# ATMEL328P.net
KiCad netlist of a schematic drawn in Altium Designer
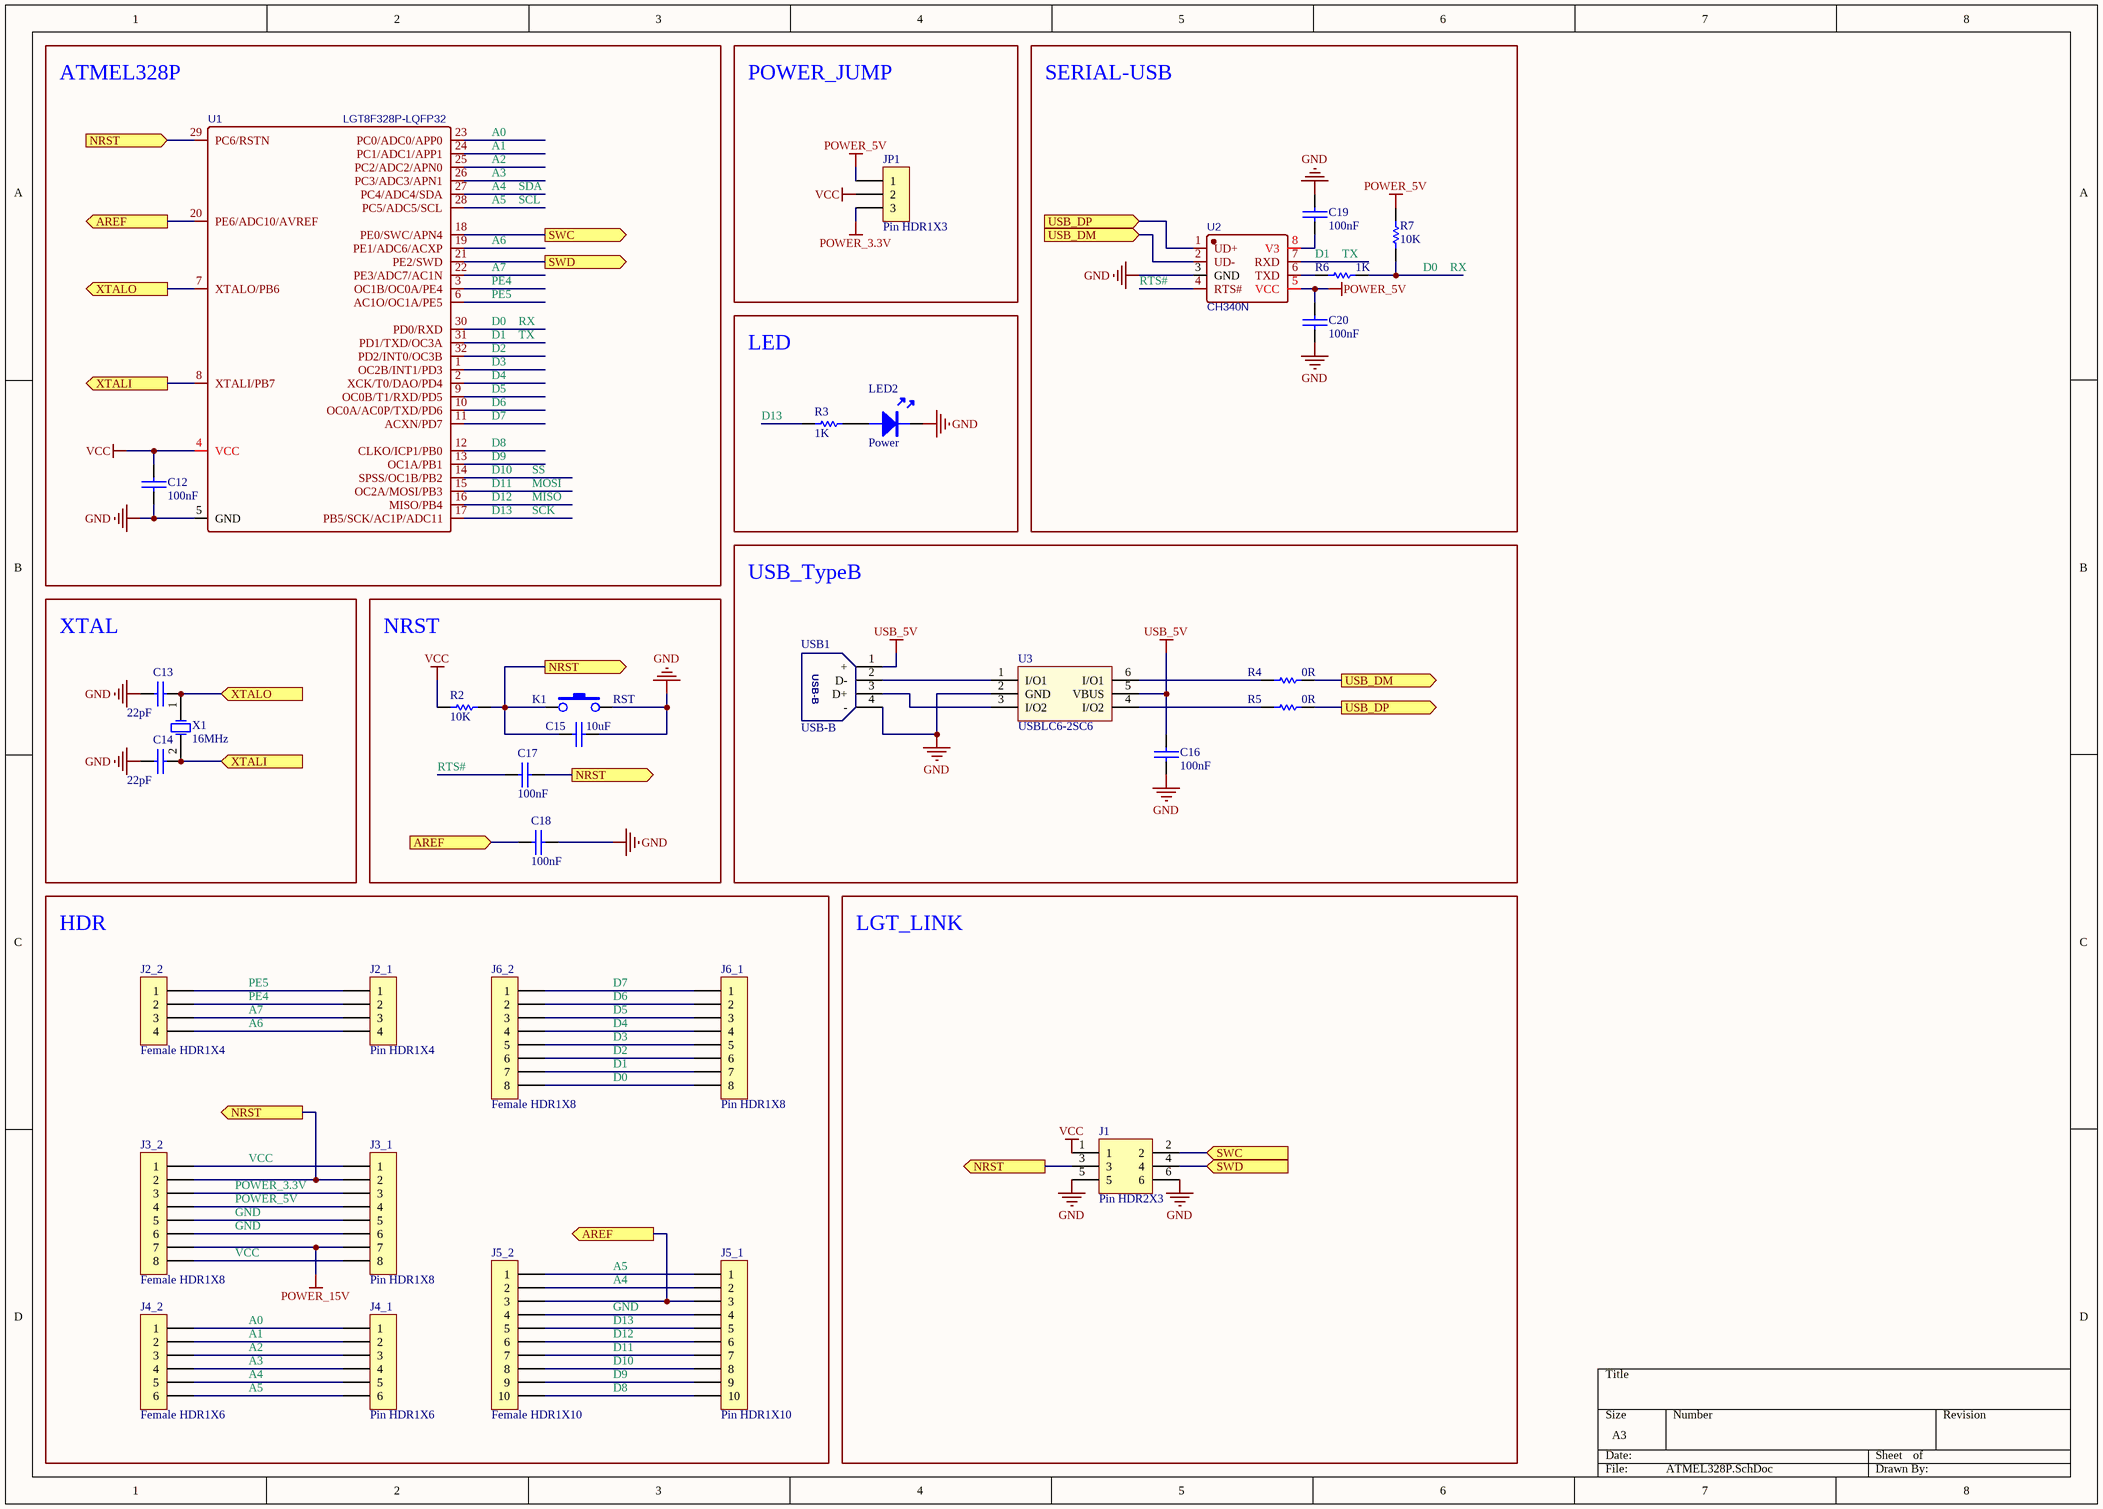
[diagram p0: ATMEL328P.SchDoc]

(export (version "E")
  (design (tool "Eeschema 10.0.6"))
  (components
    (comp (ref "C12")
      (value "100nF")
      (footprint "0603C")
      (description "无极性电容")
      (libsource (lib "电容") (part "CAP"))
    )
    (comp (ref "C13") (value "22pF") (footprint "0603C") (libsource (lib "HSunWriterIII_v3.5") (part "C")))
    (comp (ref "C14") (value "22pF") (footprint "0603C") (libsource (lib "HSunWriterIII_v3.5") (part "C")))
    (comp (ref "C15")
      (value "10uF")
      (footprint "0603C")
      (description "无极性电容")
      (libsource (lib "电容") (part "CAP"))
    )
    (comp (ref "C16")
      (value "100nF")
      (footprint "0603C")
      (description "无极性电容")
      (libsource (lib "电容") (part "CAP"))
    )
    (comp (ref "C17")
      (value "100nF")
      (footprint "0603C")
      (description "无极性电容")
      (libsource (lib "电容") (part "CAP"))
    )
    (comp (ref "C18")
      (value "100nF")
      (footprint "0603C")
      (description "无极性电容")
      (libsource (lib "电容") (part "CAP"))
    )
    (comp (ref "C19")
      (value "100nF")
      (footprint "0603C")
      (description "无极性电容")
      (libsource (lib "电容") (part "CAP"))
    )
    (comp (ref "C20")
      (value "100nF")
      (footprint "0603C")
      (description "无极性电容")
      (libsource (lib "电容") (part "CAP"))
    )
    (comp (ref "J1")
      (value "Pin HDR2X3")
      (footprint "Pin HDR2X3/2.54mm-S")
      (libsource (lib "排针") (part "Pin HDR2X3"))
    )
    (comp (ref "J2_1")
      (value "Pin HDR1X4")
      (footprint "Pin HDR1X4/2.54mm-S")
      (libsource (lib "排针") (part "Pin HDR1X4"))
    )
    (comp (ref "J2_2")
      (value "Female HDR1X4")
      (footprint "Fe-HDR1X4/2.54-S")
      (libsource (lib "排母") (part "Female HDR1X4"))
    )
    (comp (ref "J3_1")
      (value "Pin HDR1X8")
      (footprint "Pin HDR1X8/2.54mm-S")
      (libsource (lib "排针") (part "Pin HDR1X8"))
    )
    (comp (ref "J3_2")
      (value "Female HDR1X8")
      (footprint "Fe-HDR1X8/2.54-S")
      (libsource (lib "排母") (part "Female HDR1X8"))
    )
    (comp (ref "J4_1")
      (value "Pin HDR1X6")
      (footprint "Pin HDR1X6/2.54mm-S")
      (libsource (lib "排针") (part "Pin HDR1X6"))
    )
    (comp (ref "J4_2")
      (value "Female HDR1X6")
      (footprint "Fe-HDR1X6/2.54-S")
      (libsource (lib "排母") (part "Female HDR1X6"))
    )
    (comp (ref "J5_1")
      (value "Pin HDR1X10")
      (footprint "Pin HDR1X10/2.54mm-S")
      (libsource (lib "排针") (part "Pin HDR1X10"))
    )
    (comp (ref "J5_2")
      (value "Female HDR1X10")
      (footprint "Fe-HDR1X10/2.54-S")
      (libsource (lib "排母") (part "Female HDR1X10"))
    )
    (comp (ref "J6_1")
      (value "Pin HDR1X8")
      (footprint "Pin HDR1X8/2.54mm-S")
      (libsource (lib "排针") (part "Pin HDR1X8"))
    )
    (comp (ref "J6_2")
      (value "Female HDR1X8")
      (footprint "Fe-HDR1X8/2.54-S")
      (libsource (lib "排母") (part "Female HDR1X8"))
    )
    (comp (ref "JP1")
      (value "Pin HDR1X3")
      (footprint "Pin HDR1X3/2.54mm-S")
      (libsource (lib "排针") (part "Pin HDR1X3"))
    )
    (comp (ref "K1") (value "RST") (footprint "SMD-3X6X2.5") (libsource (lib "轻触开关") (part "KEY")))
    (comp (ref "LED2") (value "Power") (footprint "LED-0805G") (libsource (lib "LED") (part "LED")))
    (comp (ref "R2") (value "10K") (footprint "0603R") (libsource (lib "电阻") (part "RES")))
    (comp (ref "R3") (value "1K") (footprint "0603R") (libsource (lib "电阻") (part "RES")))
    (comp (ref "R4") (value "0R") (footprint "0603R") (libsource (lib "电阻") (part "RES")))
    (comp (ref "R5") (value "0R") (footprint "0603R") (libsource (lib "电阻") (part "RES")))
    (comp (ref "R6") (value "1K") (footprint "0603R") (libsource (lib "电阻") (part "RES")))
    (comp (ref "R7") (value "10K") (footprint "0603R") (libsource (lib "电阻") (part "RES")))
    (comp (ref "U1")
      (value "LGT8F328P-LQFP32")
      (footprint "LQFP32")
      (fields (field (name "CONTRIBUTOR") "梦之精灵影像设计协会"))
      (libsource (lib "Sheet_2023-03-16") (part "LGT8F328P-LQFP32"))
    )
    (comp (ref "U2")
      (value "CH340N")
      (footprint "SOP8")
      (fields (field (name "BOM_SUPPLIER PART") "C506813") (field (name "CONTRIBUTOR") "梦之精灵影像设计协会"))
      (libsource (lib "Sheet_2023-03-16") (part "CH340N"))
    )
    (comp (ref "U3") (value "USBLC6-2SC6") (footprint "SOT23-6") (libsource (lib "LIB") (part "USBLC6-2SC6")))
    (comp (ref "USB1") (value "USB-B") (footprint "USB-B/S_A") (libsource (lib "USB") (part "USB-B")))
    (comp (ref "X1")
      (value "16MHz")
      (footprint "OSC HC-49S")
      (description "Crystal Oscillator")
      (fields (field (name "PUBLISHER") "Altium Limited"))
      (libsource (lib "HSunWriterIII_v3.5") (part "XTAL"))
    )
  )
  (nets
    (net (code "1") (name "/A0") (class "Default")
      (node (ref "J4_1") (pin "1") (pinfunction "1_1") (pintype "passive"))
      (node (ref "J4_2") (pin "1") (pinfunction "1_1") (pintype "passive"))
      (node (ref "U1") (pin "23") (pinfunction "PC0/ADC0/APP0_23") (pintype "passive"))
    )
    (net (code "2") (name "/A1") (class "Default")
      (node (ref "J4_1") (pin "2") (pinfunction "2_2") (pintype "passive"))
      (node (ref "J4_2") (pin "2") (pinfunction "2_2") (pintype "passive"))
      (node (ref "U1") (pin "24") (pinfunction "PC1/ADC1/APP1_24") (pintype "passive"))
    )
    (net (code "3") (name "/A2") (class "Default")
      (node (ref "J4_1") (pin "3") (pinfunction "3_3") (pintype "passive"))
      (node (ref "J4_2") (pin "3") (pinfunction "3_3") (pintype "passive"))
      (node (ref "U1") (pin "25") (pinfunction "PC2/ADC2/APN0_25") (pintype "passive"))
    )
    (net (code "4") (name "/A3") (class "Default")
      (node (ref "J4_1") (pin "4") (pinfunction "4_4") (pintype "passive"))
      (node (ref "J4_2") (pin "4") (pinfunction "4_4") (pintype "passive"))
      (node (ref "U1") (pin "26") (pinfunction "PC3/ADC3/APN1_26") (pintype "passive"))
    )
    (net (code "5") (name "/A4") (class "Default")
      (node (ref "J4_1") (pin "5") (pinfunction "5_5") (pintype "passive"))
      (node (ref "J4_2") (pin "5") (pinfunction "5_5") (pintype "passive"))
      (node (ref "J5_1") (pin "2") (pinfunction "2_2") (pintype "passive"))
      (node (ref "J5_2") (pin "2") (pinfunction "2_2") (pintype "passive"))
      (node (ref "U1") (pin "27") (pinfunction "PC4/ADC4/SDA_27") (pintype "passive"))
    )
    (net (code "6") (name "/A5") (class "Default")
      (node (ref "J4_1") (pin "6") (pinfunction "6_6") (pintype "passive"))
      (node (ref "J4_2") (pin "6") (pinfunction "6_6") (pintype "passive"))
      (node (ref "J5_1") (pin "1") (pinfunction "1_1") (pintype "passive"))
      (node (ref "J5_2") (pin "1") (pinfunction "1_1") (pintype "passive"))
      (node (ref "U1") (pin "28") (pinfunction "PC5/ADC5/SCL_28") (pintype "passive"))
    )
    (net (code "7") (name "/A6") (class "Default")
      (node (ref "J2_1") (pin "4") (pinfunction "4_4") (pintype "passive"))
      (node (ref "J2_2") (pin "4") (pinfunction "4_4") (pintype "passive"))
      (node (ref "U1") (pin "19") (pinfunction "PE1/ADC6/ACXP_19") (pintype "passive"))
    )
    (net (code "8") (name "/A7") (class "Default")
      (node (ref "J2_1") (pin "3") (pinfunction "3_3") (pintype "passive"))
      (node (ref "J2_2") (pin "3") (pinfunction "3_3") (pintype "passive"))
      (node (ref "U1") (pin "22") (pinfunction "PE3/ADC7/AC1N_22") (pintype "passive"))
    )
    (net (code "9") (name "/AREF") (class "Default")
      (node (ref "C18") (pin "1") (pinfunction "1_1") (pintype "passive"))
      (node (ref "J5_1") (pin "3") (pinfunction "3_3") (pintype "passive"))
      (node (ref "J5_2") (pin "3") (pinfunction "3_3") (pintype "passive"))
      (node (ref "U1") (pin "20") (pinfunction "PE6/ADC10/AVREF_20") (pintype "passive"))
    )
    (net (code "10") (name "/D0") (class "Default")
      (node (ref "J6_1") (pin "8") (pinfunction "8_8") (pintype "passive"))
      (node (ref "J6_2") (pin "8") (pinfunction "8_8") (pintype "passive"))
      (node (ref "R6") (pin "1") (pinfunction "1_1") (pintype "passive"))
      (node (ref "R7") (pin "1") (pinfunction "1_1") (pintype "passive"))
      (node (ref "U1") (pin "30") (pinfunction "PD0/RXD_30") (pintype "passive"))
    )
    (net (code "11") (name "/D1") (class "Default")
      (node (ref "J6_1") (pin "7") (pinfunction "7_7") (pintype "passive"))
      (node (ref "J6_2") (pin "7") (pinfunction "7_7") (pintype "passive"))
      (node (ref "U1") (pin "31") (pinfunction "PD1/TXD/OC3A_31") (pintype "passive"))
      (node (ref "U2") (pin "7") (pinfunction "RXD_7") (pintype "passive"))
    )
    (net (code "12") (name "/D2") (class "Default")
      (node (ref "J6_1") (pin "6") (pinfunction "6_6") (pintype "passive"))
      (node (ref "J6_2") (pin "6") (pinfunction "6_6") (pintype "passive"))
      (node (ref "U1") (pin "32") (pinfunction "PD2/INT0/OC3B_32") (pintype "passive"))
    )
    (net (code "13") (name "/D3") (class "Default")
      (node (ref "J6_1") (pin "5") (pinfunction "5_5") (pintype "passive"))
      (node (ref "J6_2") (pin "5") (pinfunction "5_5") (pintype "passive"))
      (node (ref "U1") (pin "1") (pinfunction "OC2B/INT1/PD3_1") (pintype "passive"))
    )
    (net (code "14") (name "/D4") (class "Default")
      (node (ref "J6_1") (pin "4") (pinfunction "4_4") (pintype "passive"))
      (node (ref "J6_2") (pin "4") (pinfunction "4_4") (pintype "passive"))
      (node (ref "U1") (pin "2") (pinfunction "XCK/T0/DAO/PD4_2") (pintype "passive"))
    )
    (net (code "15") (name "/D5") (class "Default")
      (node (ref "J6_1") (pin "3") (pinfunction "3_3") (pintype "passive"))
      (node (ref "J6_2") (pin "3") (pinfunction "3_3") (pintype "passive"))
      (node (ref "U1") (pin "9") (pinfunction "OC0B/T1/RXD/PD5_9") (pintype "passive"))
    )
    (net (code "16") (name "/D6") (class "Default")
      (node (ref "J6_1") (pin "2") (pinfunction "2_2") (pintype "passive"))
      (node (ref "J6_2") (pin "2") (pinfunction "2_2") (pintype "passive"))
      (node (ref "U1") (pin "10") (pinfunction "OC0A/AC0P/TXD/PD6_10") (pintype "passive"))
    )
    (net (code "17") (name "/D7") (class "Default")
      (node (ref "J6_1") (pin "1") (pinfunction "1_1") (pintype "passive"))
      (node (ref "J6_2") (pin "1") (pinfunction "1_1") (pintype "passive"))
      (node (ref "U1") (pin "11") (pinfunction "ACXN/PD7_11") (pintype "passive"))
    )
    (net (code "18") (name "/D8") (class "Default")
      (node (ref "J5_1") (pin "10") (pinfunction "10_10") (pintype "passive"))
      (node (ref "J5_2") (pin "10") (pinfunction "10_10") (pintype "passive"))
      (node (ref "U1") (pin "12") (pinfunction "CLKO/ICP1/PB0_12") (pintype "passive"))
    )
    (net (code "19") (name "/D9") (class "Default")
      (node (ref "J5_1") (pin "9") (pinfunction "9_9") (pintype "passive"))
      (node (ref "J5_2") (pin "9") (pinfunction "9_9") (pintype "passive"))
      (node (ref "U1") (pin "13") (pinfunction "OC1A/PB1_13") (pintype "passive"))
    )
    (net (code "20") (name "/D10") (class "Default")
      (node (ref "J5_1") (pin "8") (pinfunction "8_8") (pintype "passive"))
      (node (ref "J5_2") (pin "8") (pinfunction "8_8") (pintype "passive"))
      (node (ref "U1") (pin "14") (pinfunction "SPSS/OC1B/PB2_14") (pintype "passive"))
    )
    (net (code "21") (name "/D11") (class "Default")
      (node (ref "J5_1") (pin "7") (pinfunction "7_7") (pintype "passive"))
      (node (ref "J5_2") (pin "7") (pinfunction "7_7") (pintype "passive"))
      (node (ref "U1") (pin "15") (pinfunction "OC2A/MOSI/PB3_15") (pintype "passive"))
    )
    (net (code "22") (name "/D12") (class "Default")
      (node (ref "J5_1") (pin "6") (pinfunction "6_6") (pintype "passive"))
      (node (ref "J5_2") (pin "6") (pinfunction "6_6") (pintype "passive"))
      (node (ref "U1") (pin "16") (pinfunction "MISO/PB4_16") (pintype "passive"))
    )
    (net (code "23") (name "/D13") (class "Default")
      (node (ref "J5_1") (pin "5") (pinfunction "5_5") (pintype "passive"))
      (node (ref "J5_2") (pin "5") (pinfunction "5_5") (pintype "passive"))
      (node (ref "R3") (pin "2") (pinfunction "2_2") (pintype "passive"))
      (node (ref "U1") (pin "17") (pinfunction "PB5/SCK/AC1P/ADC11_17") (pintype "passive"))
    )
    (net (code "24") (name "/NRST") (class "Default")
      (node (ref "C15") (pin "1") (pinfunction "1_1") (pintype "passive"))
      (node (ref "C17") (pin "2") (pinfunction "2_2") (pintype "passive"))
      (node (ref "J1") (pin "3") (pinfunction "3_3") (pintype "passive"))
      (node (ref "J3_1") (pin "2") (pinfunction "2_2") (pintype "passive"))
      (node (ref "J3_2") (pin "2") (pinfunction "2_2") (pintype "passive"))
      (node (ref "K1") (pin "1") (pinfunction "1_1") (pintype "passive"))
      (node (ref "R2") (pin "2") (pinfunction "2_2") (pintype "passive"))
      (node (ref "U1") (pin "29") (pinfunction "PC6/RSTN_29") (pintype "passive"))
    )
    (net (code "25") (name "/PE4") (class "Default")
      (node (ref "J2_1") (pin "2") (pinfunction "2_2") (pintype "passive"))
      (node (ref "J2_2") (pin "2") (pinfunction "2_2") (pintype "passive"))
      (node (ref "U1") (pin "3") (pinfunction "OC1B/OC0A/PE4_3") (pintype "passive"))
    )
    (net (code "26") (name "/PE5") (class "Default")
      (node (ref "J2_1") (pin "1") (pinfunction "1_1") (pintype "passive"))
      (node (ref "J2_2") (pin "1") (pinfunction "1_1") (pintype "passive"))
      (node (ref "U1") (pin "6") (pinfunction "AC1O/OC1A/PE5_6") (pintype "passive"))
    )
    (net (code "27") (name "/RTS#") (class "Default")
      (node (ref "C17") (pin "1") (pinfunction "1_1") (pintype "passive"))
      (node (ref "U2") (pin "4") (pinfunction "RTS#_4") (pintype "passive"))
    )
    (net (code "28") (name "/SWC") (class "Default")
      (node (ref "J1") (pin "2") (pinfunction "2_2") (pintype "passive"))
      (node (ref "U1") (pin "18") (pinfunction "PE0/SWC/APN4_18") (pintype "passive"))
    )
    (net (code "29") (name "/SWD") (class "Default")
      (node (ref "J1") (pin "4") (pinfunction "4_4") (pintype "passive"))
      (node (ref "U1") (pin "21") (pinfunction "PE2/SWD_21") (pintype "passive"))
    )
    (net (code "30") (name "/USB_DM") (class "Default")
      (node (ref "R4") (pin "2") (pinfunction "2_2") (pintype "passive"))
      (node (ref "U2") (pin "2") (pinfunction "UD-_2") (pintype "passive"))
    )
    (net (code "31") (name "/USB_DP") (class "Default")
      (node (ref "R5") (pin "2") (pinfunction "2_2") (pintype "passive"))
      (node (ref "U2") (pin "1") (pinfunction "UD+_1") (pintype "passive"))
    )
    (net (code "32") (name "/XTALI") (class "Default")
      (node (ref "C14") (pin "2") (pintype "passive"))
      (node (ref "U1") (pin "8") (pinfunction "XTALI/PB7_8") (pintype "passive"))
      (node (ref "X1") (pin "2") (pinfunction "OSC2_2") (pintype "passive"))
    )
    (net (code "33") (name "/XTALO") (class "Default")
      (node (ref "C13") (pin "2") (pintype "passive"))
      (node (ref "U1") (pin "7") (pinfunction "XTALO/PB6_7") (pintype "passive"))
      (node (ref "X1") (pin "1") (pinfunction "OSC1_1") (pintype "passive"))
    )
    (net (code "34") (name "GND") (class "Default")
      (node (ref "C12") (pin "1") (pinfunction "1_1") (pintype "passive"))
      (node (ref "C13") (pin "1") (pintype "passive"))
      (node (ref "C14") (pin "1") (pintype "passive"))
      (node (ref "C15") (pin "2") (pinfunction "2_2") (pintype "passive"))
      (node (ref "C16") (pin "1") (pinfunction "1_1") (pintype "passive"))
      (node (ref "C18") (pin "2") (pinfunction "2_2") (pintype "passive"))
      (node (ref "C19") (pin "2") (pinfunction "2_2") (pintype "passive"))
      (node (ref "C20") (pin "2") (pinfunction "2_2") (pintype "passive"))
      (node (ref "J1") (pin "5") (pinfunction "5_5") (pintype "passive"))
      (node (ref "J1") (pin "6") (pinfunction "6_6") (pintype "passive"))
      (node (ref "J3_1") (pin "5") (pinfunction "5_5") (pintype "passive"))
      (node (ref "J3_1") (pin "6") (pinfunction "6_6") (pintype "passive"))
      (node (ref "J3_2") (pin "5") (pinfunction "5_5") (pintype "passive"))
      (node (ref "J3_2") (pin "6") (pinfunction "6_6") (pintype "passive"))
      (node (ref "J5_1") (pin "4") (pinfunction "4_4") (pintype "passive"))
      (node (ref "J5_2") (pin "4") (pinfunction "4_4") (pintype "passive"))
      (node (ref "K1") (pin "3") (pinfunction "3_3") (pintype "passive"))
      (node (ref "LED2") (pin "K") (pinfunction "K_K") (pintype "passive"))
      (node (ref "U1") (pin "5") (pinfunction "GND_5") (pintype "passive"))
      (node (ref "U2") (pin "3") (pinfunction "GND_3") (pintype "passive"))
      (node (ref "U3") (pin "2") (pinfunction "GND_2") (pintype "power_in"))
      (node (ref "USB1") (pin "4") (pinfunction "-_4") (pintype "passive"))
    )
    (net (code "35") (name "Net-(LED2-PadA)") (class "Default")
      (node (ref "LED2") (pin "A") (pinfunction "A_A") (pintype "passive"))
      (node (ref "R3") (pin "1") (pinfunction "1_1") (pintype "passive"))
    )
    (net (code "36") (name "Net-(R4-Pad1)") (class "Default")
      (node (ref "R4") (pin "1") (pinfunction "1_1") (pintype "passive"))
      (node (ref "U3") (pin "6") (pinfunction "I/O1_6") (pintype "passive"))
    )
    (net (code "37") (name "Net-(R5-Pad1)") (class "Default")
      (node (ref "R5") (pin "1") (pinfunction "1_1") (pintype "passive"))
      (node (ref "U3") (pin "4") (pinfunction "I/O2_4") (pintype "passive"))
    )
    (net (code "38") (name "Net-(U2-TXD)") (class "Default")
      (node (ref "R6") (pin "2") (pinfunction "2_2") (pintype "passive"))
      (node (ref "U2") (pin "6") (pinfunction "TXD_6") (pintype "passive"))
    )
    (net (code "39") (name "Net-(U2-V3)") (class "Default")
      (node (ref "C19") (pin "1") (pinfunction "1_1") (pintype "passive"))
      (node (ref "U2") (pin "8") (pinfunction "V3_8") (pintype "passive"))
    )
    (net (code "40") (name "Net-(USB1-D+)") (class "Default")
      (node (ref "U3") (pin "3") (pinfunction "I/O2_3") (pintype "passive"))
      (node (ref "USB1") (pin "3") (pinfunction "D+_3") (pintype "passive"))
    )
    (net (code "41") (name "Net-(USB1-D-)") (class "Default")
      (node (ref "U3") (pin "1") (pinfunction "I/O1_1") (pintype "passive"))
      (node (ref "USB1") (pin "2") (pinfunction "D-_2") (pintype "passive"))
    )
    (net (code "42") (name "POWER_3.3V") (class "Default")
      (node (ref "J3_1") (pin "3") (pinfunction "3_3") (pintype "passive"))
      (node (ref "J3_2") (pin "3") (pinfunction "3_3") (pintype "passive"))
      (node (ref "JP1") (pin "3") (pinfunction "3_3") (pintype "passive"))
    )
    (net (code "43") (name "POWER_5V") (class "Default")
      (node (ref "C20") (pin "1") (pinfunction "1_1") (pintype "passive"))
      (node (ref "J3_1") (pin "4") (pinfunction "4_4") (pintype "passive"))
      (node (ref "J3_2") (pin "4") (pinfunction "4_4") (pintype "passive"))
      (node (ref "JP1") (pin "1") (pinfunction "1_1") (pintype "passive"))
      (node (ref "R7") (pin "2") (pinfunction "2_2") (pintype "passive"))
      (node (ref "U2") (pin "5") (pinfunction "VCC_5") (pintype "passive"))
    )
    (net (code "44") (name "POWER_15V") (class "Default")
      (node (ref "J3_1") (pin "7") (pinfunction "7_7") (pintype "passive"))
      (node (ref "J3_2") (pin "7") (pinfunction "7_7") (pintype "passive"))
    )
    (net (code "45") (name "USB_5V") (class "Default")
      (node (ref "C16") (pin "2") (pinfunction "2_2") (pintype "passive"))
      (node (ref "U3") (pin "5") (pinfunction "VBUS_5") (pintype "power_in"))
      (node (ref "USB1") (pin "1") (pinfunction "+_1") (pintype "passive"))
    )
    (net (code "46") (name "VCC") (class "Default")
      (node (ref "C12") (pin "2") (pinfunction "2_2") (pintype "passive"))
      (node (ref "J1") (pin "1") (pinfunction "1_1") (pintype "passive"))
      (node (ref "J3_1") (pin "1") (pinfunction "1_1") (pintype "passive"))
      (node (ref "J3_1") (pin "8") (pinfunction "8_8") (pintype "passive"))
      (node (ref "J3_2") (pin "1") (pinfunction "1_1") (pintype "passive"))
      (node (ref "J3_2") (pin "8") (pinfunction "8_8") (pintype "passive"))
      (node (ref "JP1") (pin "2") (pinfunction "2_2") (pintype "passive"))
      (node (ref "R2") (pin "1") (pinfunction "1_1") (pintype "passive"))
      (node (ref "U1") (pin "4") (pinfunction "VCC_4") (pintype "passive"))
    )
  )
)
